# JeffreyBJT-optocoupler.net
KiCad netlist of a schematic drawn in EAGLE
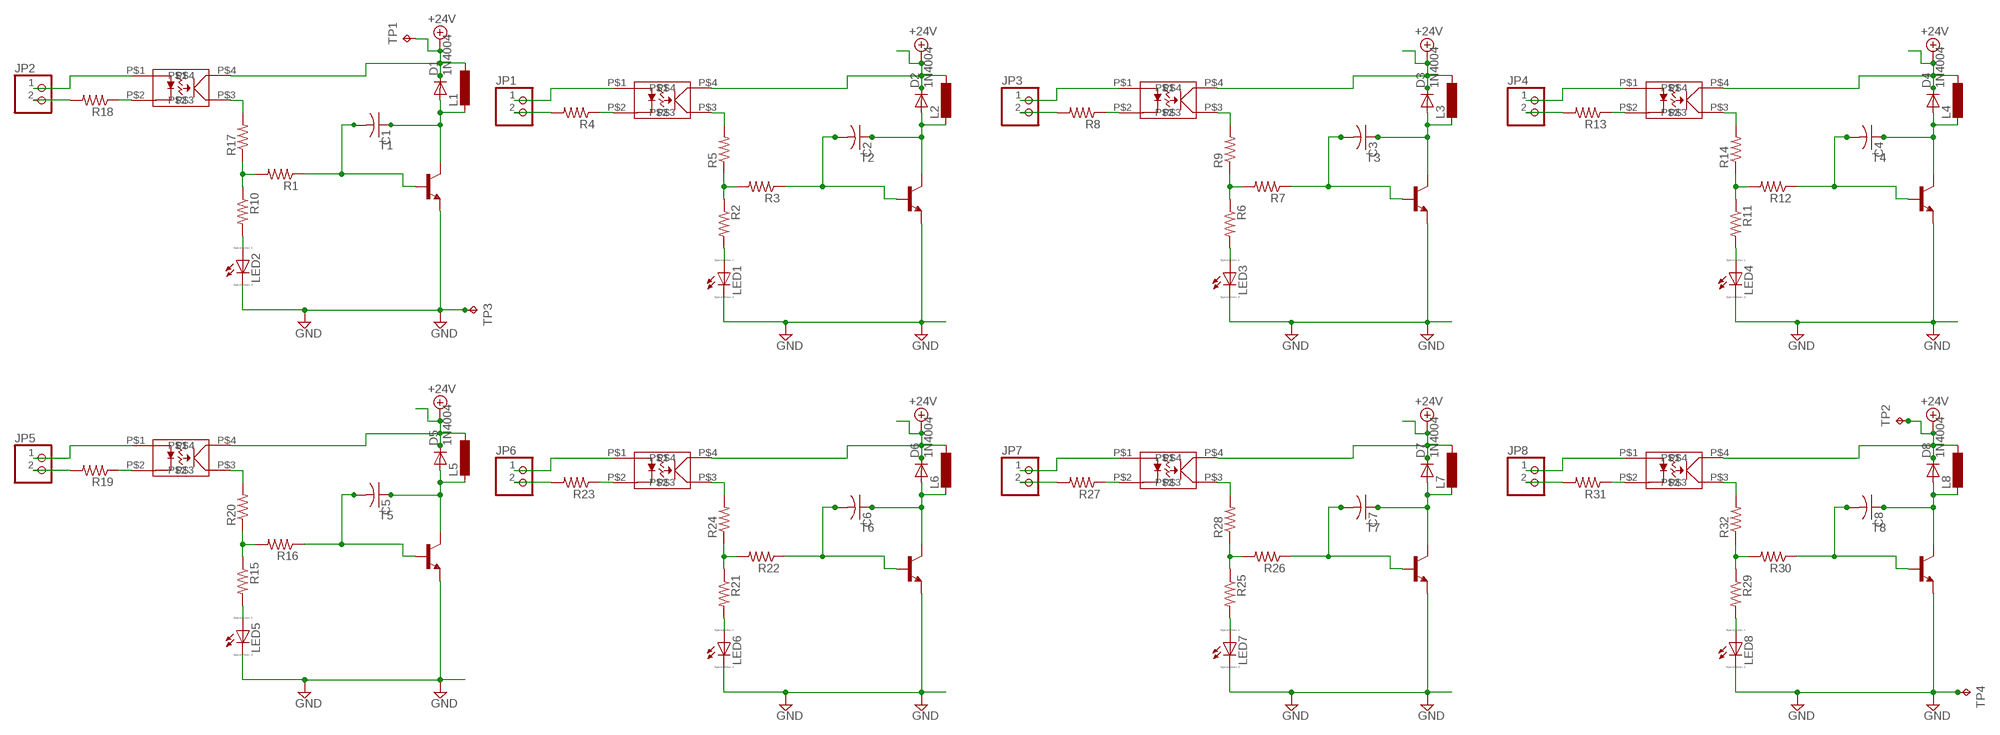
[diagram p0: schematic, sheet 1]

(export (version "E")
  (design (tool "Eeschema 10.0.6"))
  (components
    (comp (ref "C1")
      (value "C-US050-024X044")
      (footprint "eagle-import:C050-024X044")
      (libsource (lib "eagle-import") (part "C-US050-024X044"))
    )
    (comp (ref "C2")
      (value "C-US050-024X044")
      (footprint "eagle-import:C050-024X044")
      (libsource (lib "eagle-import") (part "C-US050-024X044"))
    )
    (comp (ref "C3")
      (value "C-US050-024X044")
      (footprint "eagle-import:C050-024X044")
      (libsource (lib "eagle-import") (part "C-US050-024X044"))
    )
    (comp (ref "C4")
      (value "C-US050-024X044")
      (footprint "eagle-import:C050-024X044")
      (libsource (lib "eagle-import") (part "C-US050-024X044"))
    )
    (comp (ref "C5")
      (value "C-US050-024X044")
      (footprint "eagle-import:C050-024X044")
      (libsource (lib "eagle-import") (part "C-US050-024X044"))
    )
    (comp (ref "C6")
      (value "C-US050-024X044")
      (footprint "eagle-import:C050-024X044")
      (libsource (lib "eagle-import") (part "C-US050-024X044"))
    )
    (comp (ref "C7")
      (value "C-US050-024X044")
      (footprint "eagle-import:C050-024X044")
      (libsource (lib "eagle-import") (part "C-US050-024X044"))
    )
    (comp (ref "C8")
      (value "C-US050-024X044")
      (footprint "eagle-import:C050-024X044")
      (libsource (lib "eagle-import") (part "C-US050-024X044"))
    )
    (comp (ref "D1")
      (value "1N4004")
      (footprint "eagle-import:DO41-10")
      (libsource (lib "eagle-import") (part "1N4004"))
    )
    (comp (ref "D2")
      (value "1N4004")
      (footprint "eagle-import:DO41-10")
      (libsource (lib "eagle-import") (part "1N4004"))
    )
    (comp (ref "D3")
      (value "1N4004")
      (footprint "eagle-import:DO41-10")
      (libsource (lib "eagle-import") (part "1N4004"))
    )
    (comp (ref "D4")
      (value "1N4004")
      (footprint "eagle-import:DO41-10")
      (libsource (lib "eagle-import") (part "1N4004"))
    )
    (comp (ref "D5")
      (value "1N4004")
      (footprint "eagle-import:DO41-10")
      (libsource (lib "eagle-import") (part "1N4004"))
    )
    (comp (ref "D6")
      (value "1N4004")
      (footprint "eagle-import:DO41-10")
      (libsource (lib "eagle-import") (part "1N4004"))
    )
    (comp (ref "D7")
      (value "1N4004")
      (footprint "eagle-import:DO41-10")
      (libsource (lib "eagle-import") (part "1N4004"))
    )
    (comp (ref "D8")
      (value "1N4004")
      (footprint "eagle-import:DO41-10")
      (libsource (lib "eagle-import") (part "1N4004"))
    )
    (comp (ref "JP1")
      (value "PINHD-1X2")
      (footprint "eagle-import:1X02")
      (libsource (lib "eagle-import") (part "PINHD-1X2"))
    )
    (comp (ref "JP2")
      (value "PINHD-1X2")
      (footprint "eagle-import:1X02")
      (libsource (lib "eagle-import") (part "PINHD-1X2"))
    )
    (comp (ref "JP3")
      (value "PINHD-1X2")
      (footprint "eagle-import:1X02")
      (libsource (lib "eagle-import") (part "PINHD-1X2"))
    )
    (comp (ref "JP4")
      (value "PINHD-1X2")
      (footprint "eagle-import:1X02")
      (libsource (lib "eagle-import") (part "PINHD-1X2"))
    )
    (comp (ref "JP5")
      (value "PINHD-1X2")
      (footprint "eagle-import:1X02")
      (libsource (lib "eagle-import") (part "PINHD-1X2"))
    )
    (comp (ref "JP6")
      (value "PINHD-1X2")
      (footprint "eagle-import:1X02")
      (libsource (lib "eagle-import") (part "PINHD-1X2"))
    )
    (comp (ref "JP7")
      (value "PINHD-1X2")
      (footprint "eagle-import:1X02")
      (libsource (lib "eagle-import") (part "PINHD-1X2"))
    )
    (comp (ref "JP8")
      (value "PINHD-1X2")
      (footprint "eagle-import:1X02")
      (libsource (lib "eagle-import") (part "PINHD-1X2"))
    )
    (comp (ref "L1")
      (value "L-EU0207/10")
      (footprint "eagle-import:0207_10")
      (libsource (lib "eagle-import") (part "L-EU0207/10"))
    )
    (comp (ref "L2")
      (value "L-EU0207/10")
      (footprint "eagle-import:0207_10")
      (libsource (lib "eagle-import") (part "L-EU0207/10"))
    )
    (comp (ref "L3")
      (value "L-EU0207/10")
      (footprint "eagle-import:0207_10")
      (libsource (lib "eagle-import") (part "L-EU0207/10"))
    )
    (comp (ref "L4")
      (value "L-EU0207/10")
      (footprint "eagle-import:0207_10")
      (libsource (lib "eagle-import") (part "L-EU0207/10"))
    )
    (comp (ref "L5")
      (value "L-EU0207/10")
      (footprint "eagle-import:0207_10")
      (libsource (lib "eagle-import") (part "L-EU0207/10"))
    )
    (comp (ref "L6")
      (value "L-EU0207/10")
      (footprint "eagle-import:0207_10")
      (libsource (lib "eagle-import") (part "L-EU0207/10"))
    )
    (comp (ref "L7")
      (value "L-EU0207/10")
      (footprint "eagle-import:0207_10")
      (libsource (lib "eagle-import") (part "L-EU0207/10"))
    )
    (comp (ref "L8")
      (value "L-EU0207/10")
      (footprint "eagle-import:0207_10")
      (libsource (lib "eagle-import") (part "L-EU0207/10"))
    )
    (comp (ref "LED1")
      (value "LED_ELD260")
      (footprint "eagle-import:LED_LD260")
      (libsource (lib "eagle-import") (part "LED_ELD260"))
    )
    (comp (ref "LED2")
      (value "LED_ELD260")
      (footprint "eagle-import:LED_LD260")
      (libsource (lib "eagle-import") (part "LED_ELD260"))
    )
    (comp (ref "LED3")
      (value "LED_ELD260")
      (footprint "eagle-import:LED_LD260")
      (libsource (lib "eagle-import") (part "LED_ELD260"))
    )
    (comp (ref "LED4")
      (value "LED_ELD260")
      (footprint "eagle-import:LED_LD260")
      (libsource (lib "eagle-import") (part "LED_ELD260"))
    )
    (comp (ref "LED5")
      (value "LED_ELD260")
      (footprint "eagle-import:LED_LD260")
      (libsource (lib "eagle-import") (part "LED_ELD260"))
    )
    (comp (ref "LED6")
      (value "LED_ELD260")
      (footprint "eagle-import:LED_LD260")
      (libsource (lib "eagle-import") (part "LED_ELD260"))
    )
    (comp (ref "LED7")
      (value "LED_ELD260")
      (footprint "eagle-import:LED_LD260")
      (libsource (lib "eagle-import") (part "LED_ELD260"))
    )
    (comp (ref "LED8")
      (value "LED_ELD260")
      (footprint "eagle-import:LED_LD260")
      (libsource (lib "eagle-import") (part "LED_ELD260"))
    )
    (comp (ref "R1")
      (value "R-US_0207/2V")
      (footprint "eagle-import:0207_2V")
      (libsource (lib "eagle-import") (part "R-US_0207/2V"))
    )
    (comp (ref "R2")
      (value "R-US_0207/2V")
      (footprint "eagle-import:0207_2V")
      (libsource (lib "eagle-import") (part "R-US_0207/2V"))
    )
    (comp (ref "R3")
      (value "R-US_0207/2V")
      (footprint "eagle-import:0207_2V")
      (libsource (lib "eagle-import") (part "R-US_0207/2V"))
    )
    (comp (ref "R4")
      (value "R-US_0207/2V")
      (footprint "eagle-import:0207_2V")
      (libsource (lib "eagle-import") (part "R-US_0207/2V"))
    )
    (comp (ref "R5")
      (value "R-US_0207/7")
      (footprint "eagle-import:0207_7")
      (libsource (lib "eagle-import") (part "R-US_0207/7"))
    )
    (comp (ref "R6")
      (value "R-US_0207/2V")
      (footprint "eagle-import:0207_2V")
      (libsource (lib "eagle-import") (part "R-US_0207/2V"))
    )
    (comp (ref "R7")
      (value "R-US_0207/2V")
      (footprint "eagle-import:0207_2V")
      (libsource (lib "eagle-import") (part "R-US_0207/2V"))
    )
    (comp (ref "R8")
      (value "R-US_0207/2V")
      (footprint "eagle-import:0207_2V")
      (libsource (lib "eagle-import") (part "R-US_0207/2V"))
    )
    (comp (ref "R9")
      (value "R-US_0207/7")
      (footprint "eagle-import:0207_7")
      (libsource (lib "eagle-import") (part "R-US_0207/7"))
    )
    (comp (ref "R10")
      (value "R-US_0207/2V")
      (footprint "eagle-import:0207_2V")
      (libsource (lib "eagle-import") (part "R-US_0207/2V"))
    )
    (comp (ref "R11")
      (value "R-US_0207/2V")
      (footprint "eagle-import:0207_2V")
      (libsource (lib "eagle-import") (part "R-US_0207/2V"))
    )
    (comp (ref "R12")
      (value "R-US_0207/2V")
      (footprint "eagle-import:0207_2V")
      (libsource (lib "eagle-import") (part "R-US_0207/2V"))
    )
    (comp (ref "R13")
      (value "R-US_0207/2V")
      (footprint "eagle-import:0207_2V")
      (libsource (lib "eagle-import") (part "R-US_0207/2V"))
    )
    (comp (ref "R14")
      (value "R-US_0207/7")
      (footprint "eagle-import:0207_7")
      (libsource (lib "eagle-import") (part "R-US_0207/7"))
    )
    (comp (ref "R15")
      (value "R-US_0207/2V")
      (footprint "eagle-import:0207_2V")
      (libsource (lib "eagle-import") (part "R-US_0207/2V"))
    )
    (comp (ref "R16")
      (value "R-US_0207/2V")
      (footprint "eagle-import:0207_2V")
      (libsource (lib "eagle-import") (part "R-US_0207/2V"))
    )
    (comp (ref "R17")
      (value "R-US_0207/7")
      (footprint "eagle-import:0207_7")
      (libsource (lib "eagle-import") (part "R-US_0207/7"))
    )
    (comp (ref "R18")
      (value "R-US_0207/2V")
      (footprint "eagle-import:0207_2V")
      (libsource (lib "eagle-import") (part "R-US_0207/2V"))
    )
    (comp (ref "R19")
      (value "R-US_0207/2V")
      (footprint "eagle-import:0207_2V")
      (libsource (lib "eagle-import") (part "R-US_0207/2V"))
    )
    (comp (ref "R20")
      (value "R-US_0207/7")
      (footprint "eagle-import:0207_7")
      (libsource (lib "eagle-import") (part "R-US_0207/7"))
    )
    (comp (ref "R21")
      (value "R-US_0207/2V")
      (footprint "eagle-import:0207_2V")
      (libsource (lib "eagle-import") (part "R-US_0207/2V"))
    )
    (comp (ref "R22")
      (value "R-US_0207/2V")
      (footprint "eagle-import:0207_2V")
      (libsource (lib "eagle-import") (part "R-US_0207/2V"))
    )
    (comp (ref "R23")
      (value "R-US_0207/2V")
      (footprint "eagle-import:0207_2V")
      (libsource (lib "eagle-import") (part "R-US_0207/2V"))
    )
    (comp (ref "R24")
      (value "R-US_0207/7")
      (footprint "eagle-import:0207_7")
      (libsource (lib "eagle-import") (part "R-US_0207/7"))
    )
    (comp (ref "R25")
      (value "R-US_0207/2V")
      (footprint "eagle-import:0207_2V")
      (libsource (lib "eagle-import") (part "R-US_0207/2V"))
    )
    (comp (ref "R26")
      (value "R-US_0207/2V")
      (footprint "eagle-import:0207_2V")
      (libsource (lib "eagle-import") (part "R-US_0207/2V"))
    )
    (comp (ref "R27")
      (value "R-US_0207/2V")
      (footprint "eagle-import:0207_2V")
      (libsource (lib "eagle-import") (part "R-US_0207/2V"))
    )
    (comp (ref "R28")
      (value "R-US_0207/7")
      (footprint "eagle-import:0207_7")
      (libsource (lib "eagle-import") (part "R-US_0207/7"))
    )
    (comp (ref "R29")
      (value "R-US_0207/2V")
      (footprint "eagle-import:0207_2V")
      (libsource (lib "eagle-import") (part "R-US_0207/2V"))
    )
    (comp (ref "R30")
      (value "R-US_0207/2V")
      (footprint "eagle-import:0207_2V")
      (libsource (lib "eagle-import") (part "R-US_0207/2V"))
    )
    (comp (ref "R31")
      (value "R-US_0207/2V")
      (footprint "eagle-import:0207_2V")
      (libsource (lib "eagle-import") (part "R-US_0207/2V"))
    )
    (comp (ref "R32")
      (value "R-US_0207/7")
      (footprint "eagle-import:0207_7")
      (libsource (lib "eagle-import") (part "R-US_0207/7"))
    )
    (comp (ref "T1")
      (value "-NPN-TO220V")
      (footprint "eagle-import:TO220V")
      (libsource (lib "eagle-import") (part "-NPN-TO220V"))
    )
    (comp (ref "T2")
      (value "-NPN-TO220V")
      (footprint "eagle-import:TO220V")
      (libsource (lib "eagle-import") (part "-NPN-TO220V"))
    )
    (comp (ref "T3")
      (value "-NPN-TO220V")
      (footprint "eagle-import:TO220V")
      (libsource (lib "eagle-import") (part "-NPN-TO220V"))
    )
    (comp (ref "T4")
      (value "-NPN-TO220V")
      (footprint "eagle-import:TO220V")
      (libsource (lib "eagle-import") (part "-NPN-TO220V"))
    )
    (comp (ref "T5")
      (value "-NPN-TO220V")
      (footprint "eagle-import:TO220V")
      (libsource (lib "eagle-import") (part "-NPN-TO220V"))
    )
    (comp (ref "T6")
      (value "-NPN-TO220V")
      (footprint "eagle-import:TO220V")
      (libsource (lib "eagle-import") (part "-NPN-TO220V"))
    )
    (comp (ref "T7")
      (value "-NPN-TO220V")
      (footprint "eagle-import:TO220V")
      (libsource (lib "eagle-import") (part "-NPN-TO220V"))
    )
    (comp (ref "T8")
      (value "-NPN-TO220V")
      (footprint "eagle-import:TO220V")
      (libsource (lib "eagle-import") (part "-NPN-TO220V"))
    )
    (comp (ref "TP1")
      (value "TPPAD1-13Y")
      (footprint "eagle-import:P1-13Y")
      (libsource (lib "eagle-import") (part "TPPAD1-13Y"))
    )
    (comp (ref "TP2")
      (value "TPPAD1-13Y")
      (footprint "eagle-import:P1-13Y")
      (libsource (lib "eagle-import") (part "TPPAD1-13Y"))
    )
    (comp (ref "TP3")
      (value "TPPAD1-13Y")
      (footprint "eagle-import:P1-13Y")
      (libsource (lib "eagle-import") (part "TPPAD1-13Y"))
    )
    (comp (ref "TP4")
      (value "TPPAD1-13Y")
      (footprint "eagle-import:P1-13Y")
      (libsource (lib "eagle-import") (part "TPPAD1-13Y"))
    )
    (comp (ref "U$1")
      (value "PS2501_TRU")
      (footprint "eagle-import:PS2501_TRU")
      (libsource (lib "eagle-import") (part "PS2501_TRU"))
    )
    (comp (ref "U$2")
      (value "PS2501_TRU")
      (footprint "eagle-import:PS2501_TRU")
      (libsource (lib "eagle-import") (part "PS2501_TRU"))
    )
    (comp (ref "U$3")
      (value "PS2501_TRU")
      (footprint "eagle-import:PS2501_TRU")
      (libsource (lib "eagle-import") (part "PS2501_TRU"))
    )
    (comp (ref "U$4")
      (value "PS2501_TRU")
      (footprint "eagle-import:PS2501_TRU")
      (libsource (lib "eagle-import") (part "PS2501_TRU"))
    )
    (comp (ref "U$5")
      (value "PS2501_TRU")
      (footprint "eagle-import:PS2501_TRU")
      (libsource (lib "eagle-import") (part "PS2501_TRU"))
    )
    (comp (ref "U$6")
      (value "PS2501_TRU")
      (footprint "eagle-import:PS2501_TRU")
      (libsource (lib "eagle-import") (part "PS2501_TRU"))
    )
    (comp (ref "U$7")
      (value "PS2501_TRU")
      (footprint "eagle-import:PS2501_TRU")
      (libsource (lib "eagle-import") (part "PS2501_TRU"))
    )
    (comp (ref "U$8")
      (value "PS2501_TRU")
      (footprint "eagle-import:PS2501_TRU")
      (libsource (lib "eagle-import") (part "PS2501_TRU"))
    )
  )
  (nets
    (net (code "1") (name "+24V") (class "Default")
      (node (ref "D1") (pin "C") (pinfunction "C_C") (pintype "passive"))
      (node (ref "D2") (pin "C") (pinfunction "C_C") (pintype "passive"))
      (node (ref "D3") (pin "C") (pinfunction "C_C") (pintype "passive"))
      (node (ref "D4") (pin "C") (pinfunction "C_C") (pintype "passive"))
      (node (ref "D5") (pin "C") (pinfunction "C_C") (pintype "passive"))
      (node (ref "D6") (pin "C") (pinfunction "C_C") (pintype "passive"))
      (node (ref "D7") (pin "C") (pinfunction "C_C") (pintype "passive"))
      (node (ref "D8") (pin "C") (pinfunction "C_C") (pintype "passive"))
      (node (ref "L1") (pin "1") (pinfunction "1_1") (pintype "passive"))
      (node (ref "L2") (pin "1") (pinfunction "1_1") (pintype "passive"))
      (node (ref "L3") (pin "1") (pinfunction "1_1") (pintype "passive"))
      (node (ref "L4") (pin "1") (pinfunction "1_1") (pintype "passive"))
      (node (ref "L5") (pin "1") (pinfunction "1_1") (pintype "passive"))
      (node (ref "L6") (pin "1") (pinfunction "1_1") (pintype "passive"))
      (node (ref "L7") (pin "1") (pinfunction "1_1") (pintype "passive"))
      (node (ref "L8") (pin "1") (pinfunction "1_1") (pintype "passive"))
      (node (ref "TP1") (pin "TP") (pinfunction "TP_TP") (pintype "input"))
      (node (ref "TP2") (pin "TP") (pinfunction "TP_TP") (pintype "input"))
      (node (ref "U$1") (pin "P$4") (pinfunction "P$4_P$4") (pintype "bidirectional"))
      (node (ref "U$2") (pin "P$4") (pinfunction "P$4_P$4") (pintype "bidirectional"))
      (node (ref "U$3") (pin "P$4") (pinfunction "P$4_P$4") (pintype "bidirectional"))
      (node (ref "U$4") (pin "P$4") (pinfunction "P$4_P$4") (pintype "bidirectional"))
      (node (ref "U$5") (pin "P$4") (pinfunction "P$4_P$4") (pintype "bidirectional"))
      (node (ref "U$6") (pin "P$4") (pinfunction "P$4_P$4") (pintype "bidirectional"))
      (node (ref "U$7") (pin "P$4") (pinfunction "P$4_P$4") (pintype "bidirectional"))
      (node (ref "U$8") (pin "P$4") (pinfunction "P$4_P$4") (pintype "bidirectional"))
    )
    (net (code "2") (name "GND") (class "Default")
      (node (ref "LED1") (pin "K") (pinfunction "C_K") (pintype "passive"))
      (node (ref "LED2") (pin "K") (pinfunction "C_K") (pintype "passive"))
      (node (ref "LED3") (pin "K") (pinfunction "C_K") (pintype "passive"))
      (node (ref "LED4") (pin "K") (pinfunction "C_K") (pintype "passive"))
      (node (ref "LED5") (pin "K") (pinfunction "C_K") (pintype "passive"))
      (node (ref "LED6") (pin "K") (pinfunction "C_K") (pintype "passive"))
      (node (ref "LED7") (pin "K") (pinfunction "C_K") (pintype "passive"))
      (node (ref "LED8") (pin "K") (pinfunction "C_K") (pintype "passive"))
      (node (ref "T1") (pin "3") (pinfunction "E_3") (pintype "passive"))
      (node (ref "T2") (pin "3") (pinfunction "E_3") (pintype "passive"))
      (node (ref "T3") (pin "3") (pinfunction "E_3") (pintype "passive"))
      (node (ref "T4") (pin "3") (pinfunction "E_3") (pintype "passive"))
      (node (ref "T5") (pin "3") (pinfunction "E_3") (pintype "passive"))
      (node (ref "T6") (pin "3") (pinfunction "E_3") (pintype "passive"))
      (node (ref "T7") (pin "3") (pinfunction "E_3") (pintype "passive"))
      (node (ref "T8") (pin "3") (pinfunction "E_3") (pintype "passive"))
      (node (ref "TP3") (pin "TP") (pinfunction "TP_TP") (pintype "input"))
      (node (ref "TP4") (pin "TP") (pinfunction "TP_TP") (pintype "input"))
    )
    (net (code "3") (name "Net-(JP1-Pad1)") (class "Default")
      (node (ref "JP1") (pin "1") (pinfunction "1_1") (pintype "passive"))
      (node (ref "U$2") (pin "P$1") (pinfunction "P$1_P$1") (pintype "bidirectional"))
    )
    (net (code "4") (name "Net-(JP1-Pad2)") (class "Default")
      (node (ref "JP1") (pin "2") (pinfunction "2_2") (pintype "passive"))
      (node (ref "R4") (pin "2") (pinfunction "2_2") (pintype "passive"))
    )
    (net (code "5") (name "Net-(JP2-Pad1)") (class "Default")
      (node (ref "JP2") (pin "1") (pinfunction "1_1") (pintype "passive"))
      (node (ref "U$1") (pin "P$1") (pinfunction "P$1_P$1") (pintype "bidirectional"))
    )
    (net (code "6") (name "Net-(JP2-Pad2)") (class "Default")
      (node (ref "JP2") (pin "2") (pinfunction "2_2") (pintype "passive"))
      (node (ref "R18") (pin "2") (pinfunction "2_2") (pintype "passive"))
    )
    (net (code "7") (name "Net-(JP3-Pad1)") (class "Default")
      (node (ref "JP3") (pin "1") (pinfunction "1_1") (pintype "passive"))
      (node (ref "U$3") (pin "P$1") (pinfunction "P$1_P$1") (pintype "bidirectional"))
    )
    (net (code "8") (name "Net-(JP3-Pad2)") (class "Default")
      (node (ref "JP3") (pin "2") (pinfunction "2_2") (pintype "passive"))
      (node (ref "R8") (pin "2") (pinfunction "2_2") (pintype "passive"))
    )
    (net (code "9") (name "Net-(JP4-Pad1)") (class "Default")
      (node (ref "JP4") (pin "1") (pinfunction "1_1") (pintype "passive"))
      (node (ref "U$4") (pin "P$1") (pinfunction "P$1_P$1") (pintype "bidirectional"))
    )
    (net (code "10") (name "Net-(JP4-Pad2)") (class "Default")
      (node (ref "JP4") (pin "2") (pinfunction "2_2") (pintype "passive"))
      (node (ref "R13") (pin "2") (pinfunction "2_2") (pintype "passive"))
    )
    (net (code "11") (name "Net-(JP5-Pad1)") (class "Default")
      (node (ref "JP5") (pin "1") (pinfunction "1_1") (pintype "passive"))
      (node (ref "U$5") (pin "P$1") (pinfunction "P$1_P$1") (pintype "bidirectional"))
    )
    (net (code "12") (name "Net-(JP5-Pad2)") (class "Default")
      (node (ref "JP5") (pin "2") (pinfunction "2_2") (pintype "passive"))
      (node (ref "R19") (pin "2") (pinfunction "2_2") (pintype "passive"))
    )
    (net (code "13") (name "Net-(JP6-Pad1)") (class "Default")
      (node (ref "JP6") (pin "1") (pinfunction "1_1") (pintype "passive"))
      (node (ref "U$6") (pin "P$1") (pinfunction "P$1_P$1") (pintype "bidirectional"))
    )
    (net (code "14") (name "Net-(JP6-Pad2)") (class "Default")
      (node (ref "JP6") (pin "2") (pinfunction "2_2") (pintype "passive"))
      (node (ref "R23") (pin "2") (pinfunction "2_2") (pintype "passive"))
    )
    (net (code "15") (name "Net-(JP7-Pad1)") (class "Default")
      (node (ref "JP7") (pin "1") (pinfunction "1_1") (pintype "passive"))
      (node (ref "U$7") (pin "P$1") (pinfunction "P$1_P$1") (pintype "bidirectional"))
    )
    (net (code "16") (name "Net-(JP7-Pad2)") (class "Default")
      (node (ref "JP7") (pin "2") (pinfunction "2_2") (pintype "passive"))
      (node (ref "R27") (pin "2") (pinfunction "2_2") (pintype "passive"))
    )
    (net (code "17") (name "Net-(JP8-Pad1)") (class "Default")
      (node (ref "JP8") (pin "1") (pinfunction "1_1") (pintype "passive"))
      (node (ref "U$8") (pin "P$1") (pinfunction "P$1_P$1") (pintype "bidirectional"))
    )
    (net (code "18") (name "Net-(JP8-Pad2)") (class "Default")
      (node (ref "JP8") (pin "2") (pinfunction "2_2") (pintype "passive"))
      (node (ref "R31") (pin "2") (pinfunction "2_2") (pintype "passive"))
    )
    (net (code "19") (name "Net-(LED1-PadA)") (class "Default")
      (node (ref "LED1") (pin "A") (pinfunction "A_A") (pintype "passive"))
      (node (ref "R2") (pin "2") (pinfunction "2_2") (pintype "passive"))
    )
    (net (code "20") (name "Net-(LED2-PadA)") (class "Default")
      (node (ref "LED2") (pin "A") (pinfunction "A_A") (pintype "passive"))
      (node (ref "R10") (pin "2") (pinfunction "2_2") (pintype "passive"))
    )
    (net (code "21") (name "Net-(LED3-PadA)") (class "Default")
      (node (ref "LED3") (pin "A") (pinfunction "A_A") (pintype "passive"))
      (node (ref "R6") (pin "2") (pinfunction "2_2") (pintype "passive"))
    )
    (net (code "22") (name "Net-(LED4-PadA)") (class "Default")
      (node (ref "LED4") (pin "A") (pinfunction "A_A") (pintype "passive"))
      (node (ref "R11") (pin "2") (pinfunction "2_2") (pintype "passive"))
    )
    (net (code "23") (name "Net-(LED5-PadA)") (class "Default")
      (node (ref "LED5") (pin "A") (pinfunction "A_A") (pintype "passive"))
      (node (ref "R15") (pin "2") (pinfunction "2_2") (pintype "passive"))
    )
    (net (code "24") (name "Net-(LED6-PadA)") (class "Default")
      (node (ref "LED6") (pin "A") (pinfunction "A_A") (pintype "passive"))
      (node (ref "R21") (pin "2") (pinfunction "2_2") (pintype "passive"))
    )
    (net (code "25") (name "Net-(LED7-PadA)") (class "Default")
      (node (ref "LED7") (pin "A") (pinfunction "A_A") (pintype "passive"))
      (node (ref "R25") (pin "2") (pinfunction "2_2") (pintype "passive"))
    )
    (net (code "26") (name "Net-(LED8-PadA)") (class "Default")
      (node (ref "LED8") (pin "A") (pinfunction "A_A") (pintype "passive"))
      (node (ref "R29") (pin "2") (pinfunction "2_2") (pintype "passive"))
    )
    (net (code "27") (name "Net-(R1-Pad2)") (class "Default")
      (node (ref "R1") (pin "2") (pinfunction "2_2") (pintype "passive"))
      (node (ref "R10") (pin "1") (pinfunction "1_1") (pintype "passive"))
      (node (ref "R17") (pin "1") (pinfunction "1_1") (pintype "passive"))
    )
    (net (code "28") (name "Net-(R2-Pad1)") (class "Default")
      (node (ref "R2") (pin "1") (pinfunction "1_1") (pintype "passive"))
      (node (ref "R3") (pin "2") (pinfunction "2_2") (pintype "passive"))
      (node (ref "R5") (pin "1") (pinfunction "1_1") (pintype "passive"))
    )
    (net (code "29") (name "Net-(R4-Pad1)") (class "Default")
      (node (ref "R4") (pin "1") (pinfunction "1_1") (pintype "passive"))
      (node (ref "U$2") (pin "P$2") (pinfunction "P$2_P$2") (pintype "bidirectional"))
    )
    (net (code "30") (name "Net-(R5-Pad2)") (class "Default")
      (node (ref "R5") (pin "2") (pinfunction "2_2") (pintype "passive"))
      (node (ref "U$2") (pin "P$3") (pinfunction "P$3_P$3") (pintype "bidirectional"))
    )
    (net (code "31") (name "Net-(R6-Pad1)") (class "Default")
      (node (ref "R6") (pin "1") (pinfunction "1_1") (pintype "passive"))
      (node (ref "R7") (pin "2") (pinfunction "2_2") (pintype "passive"))
      (node (ref "R9") (pin "1") (pinfunction "1_1") (pintype "passive"))
    )
    (net (code "32") (name "Net-(R8-Pad1)") (class "Default")
      (node (ref "R8") (pin "1") (pinfunction "1_1") (pintype "passive"))
      (node (ref "U$3") (pin "P$2") (pinfunction "P$2_P$2") (pintype "bidirectional"))
    )
    (net (code "33") (name "Net-(R9-Pad2)") (class "Default")
      (node (ref "R9") (pin "2") (pinfunction "2_2") (pintype "passive"))
      (node (ref "U$3") (pin "P$3") (pinfunction "P$3_P$3") (pintype "bidirectional"))
    )
    (net (code "34") (name "Net-(R11-Pad1)") (class "Default")
      (node (ref "R11") (pin "1") (pinfunction "1_1") (pintype "passive"))
      (node (ref "R12") (pin "2") (pinfunction "2_2") (pintype "passive"))
      (node (ref "R14") (pin "1") (pinfunction "1_1") (pintype "passive"))
    )
    (net (code "35") (name "Net-(R13-Pad1)") (class "Default")
      (node (ref "R13") (pin "1") (pinfunction "1_1") (pintype "passive"))
      (node (ref "U$4") (pin "P$2") (pinfunction "P$2_P$2") (pintype "bidirectional"))
    )
    (net (code "36") (name "Net-(R14-Pad2)") (class "Default")
      (node (ref "R14") (pin "2") (pinfunction "2_2") (pintype "passive"))
      (node (ref "U$4") (pin "P$3") (pinfunction "P$3_P$3") (pintype "bidirectional"))
    )
    (net (code "37") (name "Net-(R15-Pad1)") (class "Default")
      (node (ref "R15") (pin "1") (pinfunction "1_1") (pintype "passive"))
      (node (ref "R16") (pin "2") (pinfunction "2_2") (pintype "passive"))
      (node (ref "R20") (pin "1") (pinfunction "1_1") (pintype "passive"))
    )
    (net (code "38") (name "Net-(R17-Pad2)") (class "Default")
      (node (ref "R17") (pin "2") (pinfunction "2_2") (pintype "passive"))
      (node (ref "U$1") (pin "P$3") (pinfunction "P$3_P$3") (pintype "bidirectional"))
    )
    (net (code "39") (name "Net-(R18-Pad1)") (class "Default")
      (node (ref "R18") (pin "1") (pinfunction "1_1") (pintype "passive"))
      (node (ref "U$1") (pin "P$2") (pinfunction "P$2_P$2") (pintype "bidirectional"))
    )
    (net (code "40") (name "Net-(R19-Pad1)") (class "Default")
      (node (ref "R19") (pin "1") (pinfunction "1_1") (pintype "passive"))
      (node (ref "U$5") (pin "P$2") (pinfunction "P$2_P$2") (pintype "bidirectional"))
    )
    (net (code "41") (name "Net-(R20-Pad2)") (class "Default")
      (node (ref "R20") (pin "2") (pinfunction "2_2") (pintype "passive"))
      (node (ref "U$5") (pin "P$3") (pinfunction "P$3_P$3") (pintype "bidirectional"))
    )
    (net (code "42") (name "Net-(R21-Pad1)") (class "Default")
      (node (ref "R21") (pin "1") (pinfunction "1_1") (pintype "passive"))
      (node (ref "R22") (pin "2") (pinfunction "2_2") (pintype "passive"))
      (node (ref "R24") (pin "1") (pinfunction "1_1") (pintype "passive"))
    )
    (net (code "43") (name "Net-(R23-Pad1)") (class "Default")
      (node (ref "R23") (pin "1") (pinfunction "1_1") (pintype "passive"))
      (node (ref "U$6") (pin "P$2") (pinfunction "P$2_P$2") (pintype "bidirectional"))
    )
    (net (code "44") (name "Net-(R24-Pad2)") (class "Default")
      (node (ref "R24") (pin "2") (pinfunction "2_2") (pintype "passive"))
      (node (ref "U$6") (pin "P$3") (pinfunction "P$3_P$3") (pintype "bidirectional"))
    )
    (net (code "45") (name "Net-(R25-Pad1)") (class "Default")
      (node (ref "R25") (pin "1") (pinfunction "1_1") (pintype "passive"))
      (node (ref "R26") (pin "2") (pinfunction "2_2") (pintype "passive"))
      (node (ref "R28") (pin "1") (pinfunction "1_1") (pintype "passive"))
    )
    (net (code "46") (name "Net-(R27-Pad1)") (class "Default")
      (node (ref "R27") (pin "1") (pinfunction "1_1") (pintype "passive"))
      (node (ref "U$7") (pin "P$2") (pinfunction "P$2_P$2") (pintype "bidirectional"))
    )
    (net (code "47") (name "Net-(R28-Pad2)") (class "Default")
      (node (ref "R28") (pin "2") (pinfunction "2_2") (pintype "passive"))
      (node (ref "U$7") (pin "P$3") (pinfunction "P$3_P$3") (pintype "bidirectional"))
    )
    (net (code "48") (name "Net-(R29-Pad1)") (class "Default")
      (node (ref "R29") (pin "1") (pinfunction "1_1") (pintype "passive"))
      (node (ref "R30") (pin "2") (pinfunction "2_2") (pintype "passive"))
      (node (ref "R32") (pin "1") (pinfunction "1_1") (pintype "passive"))
    )
    (net (code "49") (name "Net-(R31-Pad1)") (class "Default")
      (node (ref "R31") (pin "1") (pinfunction "1_1") (pintype "passive"))
      (node (ref "U$8") (pin "P$2") (pinfunction "P$2_P$2") (pintype "bidirectional"))
    )
    (net (code "50") (name "Net-(R32-Pad2)") (class "Default")
      (node (ref "R32") (pin "2") (pinfunction "2_2") (pintype "passive"))
      (node (ref "U$8") (pin "P$3") (pinfunction "P$3_P$3") (pintype "bidirectional"))
    )
    (net (code "51") (name "Net-(T1-B)") (class "Default")
      (node (ref "C1") (pin "2") (pinfunction "2_2") (pintype "passive"))
      (node (ref "R1") (pin "1") (pinfunction "1_1") (pintype "passive"))
      (node (ref "T1") (pin "1") (pinfunction "B_1") (pintype "passive"))
    )
    (net (code "52") (name "Net-(T1-C)") (class "Default")
      (node (ref "C1") (pin "1") (pinfunction "1_1") (pintype "passive"))
      (node (ref "D1") (pin "A") (pinfunction "A_A") (pintype "passive"))
      (node (ref "L1") (pin "2") (pinfunction "2_2") (pintype "passive"))
      (node (ref "T1") (pin "2") (pinfunction "C_2") (pintype "passive"))
    )
    (net (code "53") (name "Net-(T2-B)") (class "Default")
      (node (ref "C2") (pin "2") (pinfunction "2_2") (pintype "passive"))
      (node (ref "R3") (pin "1") (pinfunction "1_1") (pintype "passive"))
      (node (ref "T2") (pin "1") (pinfunction "B_1") (pintype "passive"))
    )
    (net (code "54") (name "Net-(T2-C)") (class "Default")
      (node (ref "C2") (pin "1") (pinfunction "1_1") (pintype "passive"))
      (node (ref "D2") (pin "A") (pinfunction "A_A") (pintype "passive"))
      (node (ref "L2") (pin "2") (pinfunction "2_2") (pintype "passive"))
      (node (ref "T2") (pin "2") (pinfunction "C_2") (pintype "passive"))
    )
    (net (code "55") (name "Net-(T3-B)") (class "Default")
      (node (ref "C3") (pin "2") (pinfunction "2_2") (pintype "passive"))
      (node (ref "R7") (pin "1") (pinfunction "1_1") (pintype "passive"))
      (node (ref "T3") (pin "1") (pinfunction "B_1") (pintype "passive"))
    )
    (net (code "56") (name "Net-(T3-C)") (class "Default")
      (node (ref "C3") (pin "1") (pinfunction "1_1") (pintype "passive"))
      (node (ref "D3") (pin "A") (pinfunction "A_A") (pintype "passive"))
      (node (ref "L3") (pin "2") (pinfunction "2_2") (pintype "passive"))
      (node (ref "T3") (pin "2") (pinfunction "C_2") (pintype "passive"))
    )
    (net (code "57") (name "Net-(T4-B)") (class "Default")
      (node (ref "C4") (pin "2") (pinfunction "2_2") (pintype "passive"))
      (node (ref "R12") (pin "1") (pinfunction "1_1") (pintype "passive"))
      (node (ref "T4") (pin "1") (pinfunction "B_1") (pintype "passive"))
    )
    (net (code "58") (name "Net-(T4-C)") (class "Default")
      (node (ref "C4") (pin "1") (pinfunction "1_1") (pintype "passive"))
      (node (ref "D4") (pin "A") (pinfunction "A_A") (pintype "passive"))
      (node (ref "L4") (pin "2") (pinfunction "2_2") (pintype "passive"))
      (node (ref "T4") (pin "2") (pinfunction "C_2") (pintype "passive"))
    )
    (net (code "59") (name "Net-(T5-B)") (class "Default")
      (node (ref "C5") (pin "2") (pinfunction "2_2") (pintype "passive"))
      (node (ref "R16") (pin "1") (pinfunction "1_1") (pintype "passive"))
      (node (ref "T5") (pin "1") (pinfunction "B_1") (pintype "passive"))
    )
    (net (code "60") (name "Net-(T5-C)") (class "Default")
      (node (ref "C5") (pin "1") (pinfunction "1_1") (pintype "passive"))
      (node (ref "D5") (pin "A") (pinfunction "A_A") (pintype "passive"))
      (node (ref "L5") (pin "2") (pinfunction "2_2") (pintype "passive"))
      (node (ref "T5") (pin "2") (pinfunction "C_2") (pintype "passive"))
    )
    (net (code "61") (name "Net-(T6-B)") (class "Default")
      (node (ref "C6") (pin "2") (pinfunction "2_2") (pintype "passive"))
      (node (ref "R22") (pin "1") (pinfunction "1_1") (pintype "passive"))
      (node (ref "T6") (pin "1") (pinfunction "B_1") (pintype "passive"))
    )
    (net (code "62") (name "Net-(T6-C)") (class "Default")
      (node (ref "C6") (pin "1") (pinfunction "1_1") (pintype "passive"))
      (node (ref "D6") (pin "A") (pinfunction "A_A") (pintype "passive"))
      (node (ref "L6") (pin "2") (pinfunction "2_2") (pintype "passive"))
      (node (ref "T6") (pin "2") (pinfunction "C_2") (pintype "passive"))
    )
    (net (code "63") (name "Net-(T7-B)") (class "Default")
      (node (ref "C7") (pin "2") (pinfunction "2_2") (pintype "passive"))
      (node (ref "R26") (pin "1") (pinfunction "1_1") (pintype "passive"))
      (node (ref "T7") (pin "1") (pinfunction "B_1") (pintype "passive"))
    )
    (net (code "64") (name "Net-(T7-C)") (class "Default")
      (node (ref "C7") (pin "1") (pinfunction "1_1") (pintype "passive"))
      (node (ref "D7") (pin "A") (pinfunction "A_A") (pintype "passive"))
      (node (ref "L7") (pin "2") (pinfunction "2_2") (pintype "passive"))
      (node (ref "T7") (pin "2") (pinfunction "C_2") (pintype "passive"))
    )
    (net (code "65") (name "Net-(T8-B)") (class "Default")
      (node (ref "C8") (pin "2") (pinfunction "2_2") (pintype "passive"))
      (node (ref "R30") (pin "1") (pinfunction "1_1") (pintype "passive"))
      (node (ref "T8") (pin "1") (pinfunction "B_1") (pintype "passive"))
    )
    (net (code "66") (name "Net-(T8-C)") (class "Default")
      (node (ref "C8") (pin "1") (pinfunction "1_1") (pintype "passive"))
      (node (ref "D8") (pin "A") (pinfunction "A_A") (pintype "passive"))
      (node (ref "L8") (pin "2") (pinfunction "2_2") (pintype "passive"))
      (node (ref "T8") (pin "2") (pinfunction "C_2") (pintype "passive"))
    )
  )
)
